# 09_LMS2_RF.net
KiCad netlist of a schematic drawn in Altium Designer
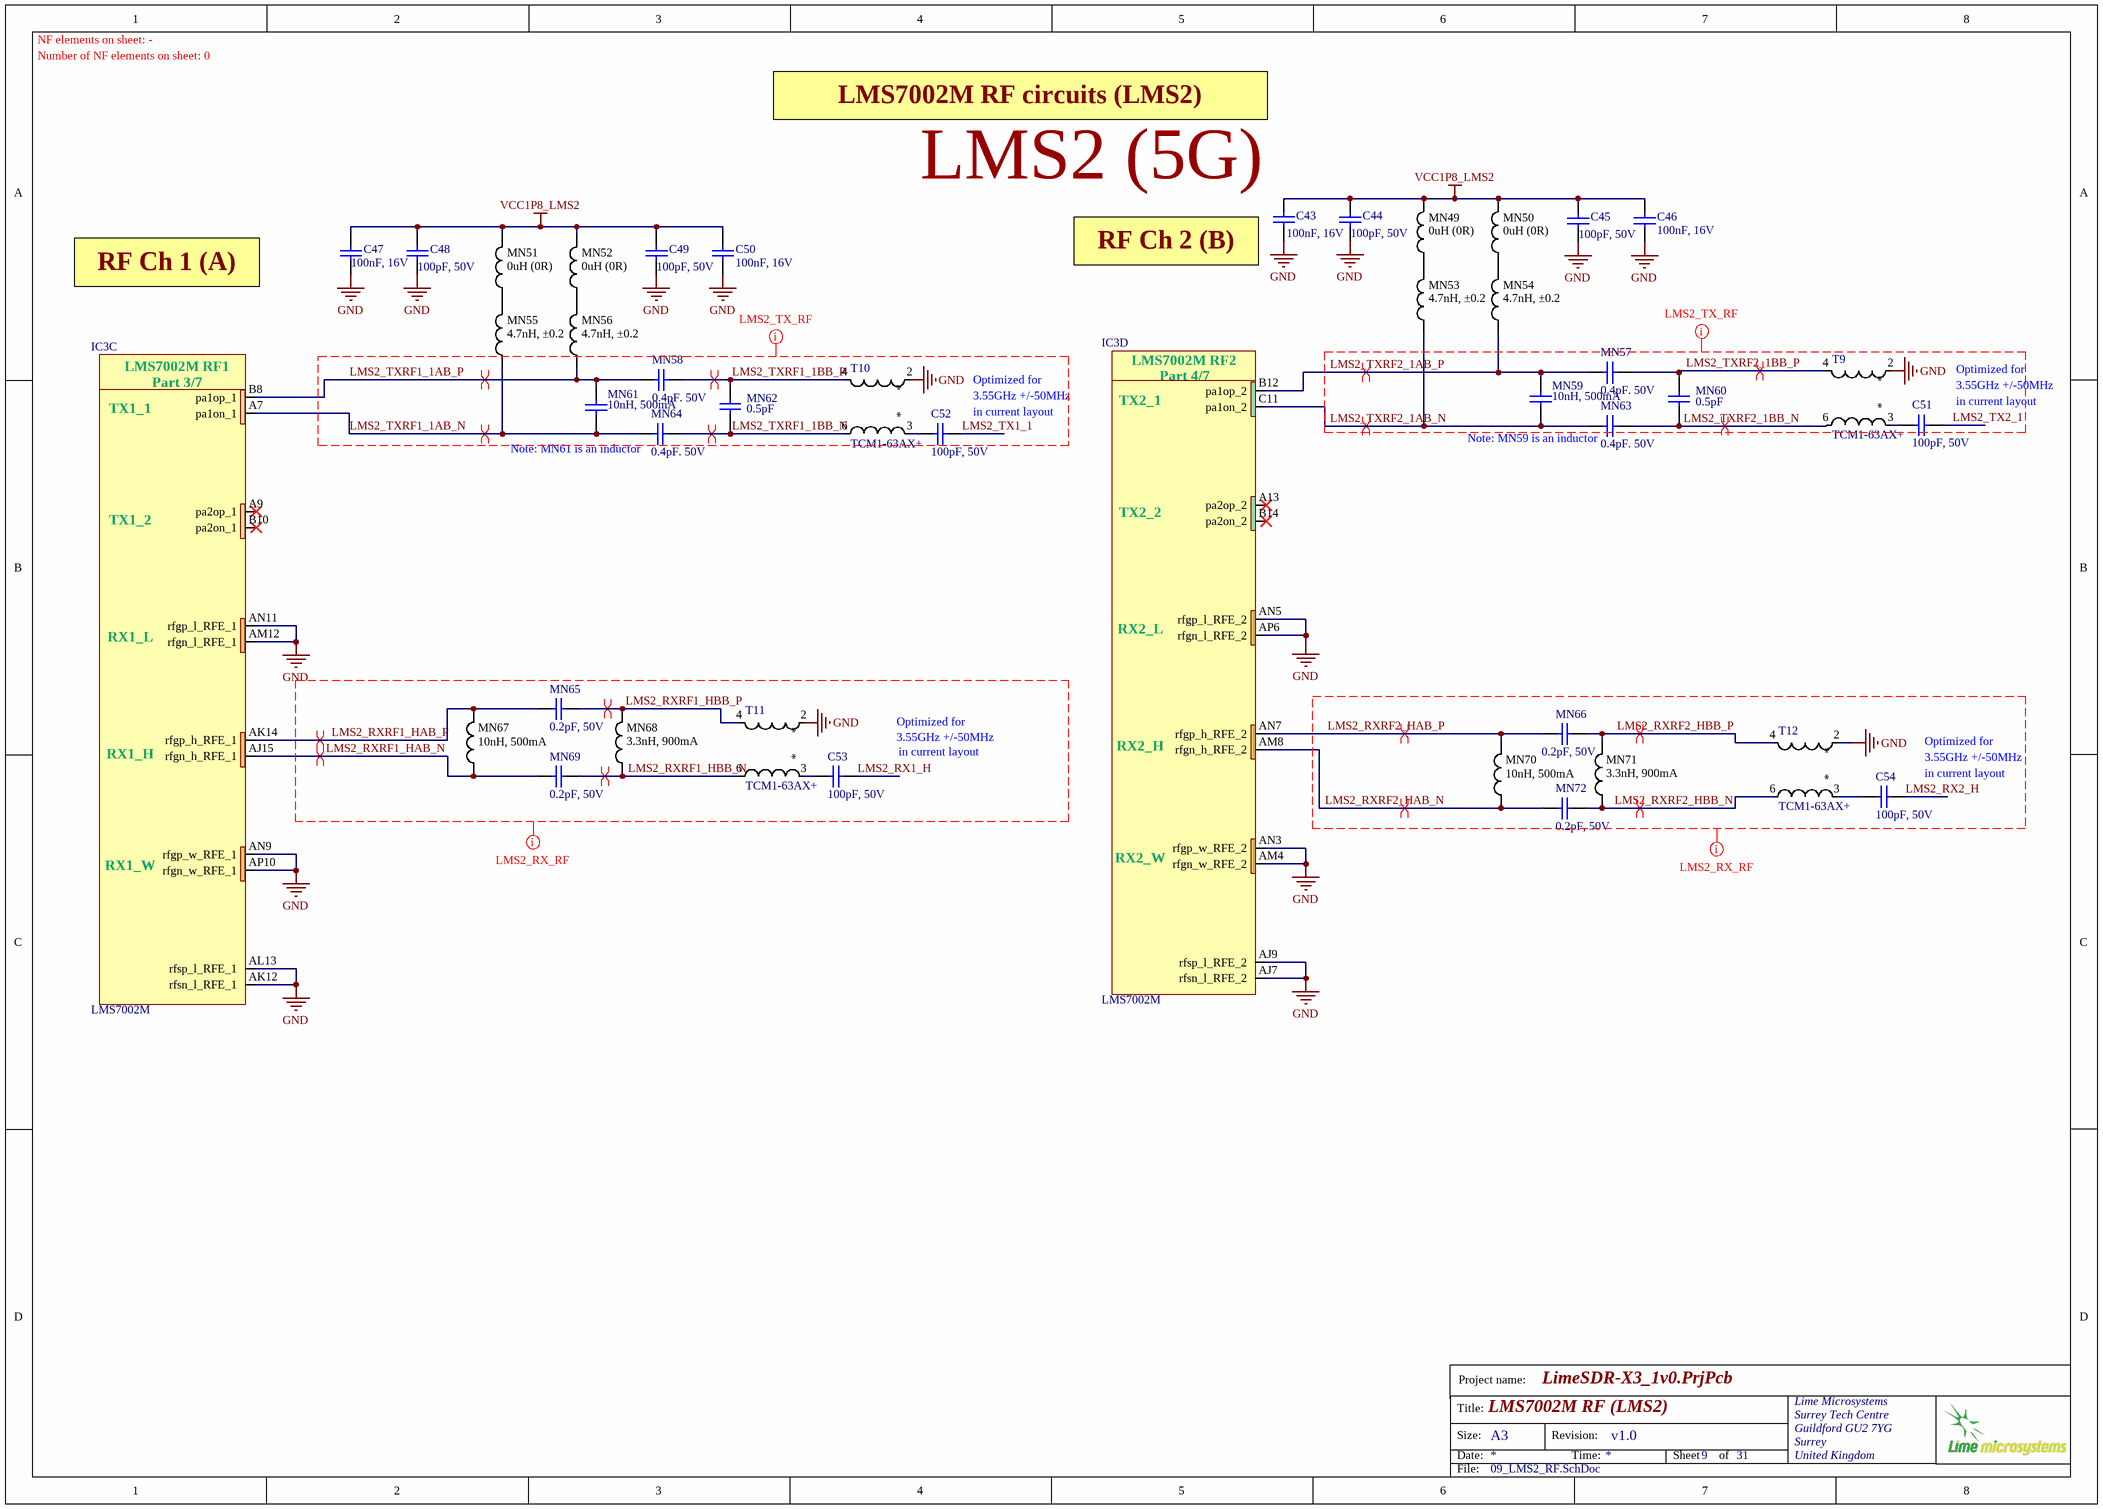
[diagram p0: 09_LMS2_RF.SchDoc]

(export (version "E")
  (design (tool "Eeschema 10.0.6"))
  (components
    (comp (ref "C43")
      (value "100nF, 16V")
      (footprint "CAP0402")
      (fields (field (name "MANUFACTURER") "Murata Electronics") (field (name "TOLERANCE") "10 %"))
      (libsource (lib "LimeMicroAltiumLib_schLib") (part "Cap_0402"))
    )
    (comp (ref "C44")
      (value "100pF, 50V")
      (footprint "CAP0402")
      (fields (field (name "MANUFACTURER") "Yageo") (field (name "TOLERANCE") "±5%"))
      (libsource (lib "") (part "Cap_0402_5"))
    )
    (comp (ref "C45")
      (value "100pF, 50V")
      (footprint "CAP0402")
      (fields (field (name "MANUFACTURER") "Yageo") (field (name "TOLERANCE") "±5%"))
      (libsource (lib "") (part "Cap_0402_5"))
    )
    (comp (ref "C46")
      (value "100nF, 16V")
      (footprint "CAP0402")
      (fields (field (name "MANUFACTURER") "Murata Electronics") (field (name "TOLERANCE") "10 %"))
      (libsource (lib "LimeMicroAltiumLib_schLib") (part "Cap_0402"))
    )
    (comp (ref "C47")
      (value "100nF, 16V")
      (footprint "CAP0402")
      (fields (field (name "MANUFACTURER") "Murata Electronics") (field (name "TOLERANCE") "10 %"))
      (libsource (lib "") (part "Cap_0402_2"))
    )
    (comp (ref "C48")
      (value "100pF, 50V")
      (footprint "CAP0402")
      (fields (field (name "MANUFACTURER") "Yageo") (field (name "TOLERANCE") "±5%"))
      (libsource (lib "") (part "Cap_0402_5"))
    )
    (comp (ref "C49")
      (value "100pF, 50V")
      (footprint "CAP0402")
      (fields (field (name "MANUFACTURER") "Yageo") (field (name "TOLERANCE") "±5%"))
      (libsource (lib "") (part "Cap_0402_5"))
    )
    (comp (ref "C50")
      (value "100nF, 16V")
      (footprint "CAP0402")
      (fields (field (name "MANUFACTURER") "Murata Electronics") (field (name "TOLERANCE") "10 %"))
      (libsource (lib "") (part "Cap_0402_2"))
    )
    (comp (ref "C51")
      (value "100pF, 50V")
      (footprint "CAP0402")
      (fields (field (name "TOLERANCE") "±5%") (field (name "MANUFACTURER") "Yageo"))
      (libsource (lib "") (part "Cap_0402_2"))
    )
    (comp (ref "C52")
      (value "100pF, 50V")
      (footprint "CAP0402")
      (fields (field (name "TOLERANCE") "±5%") (field (name "MANUFACTURER") "Yageo"))
      (libsource (lib "") (part "Cap_0402_2"))
    )
    (comp (ref "C53")
      (value "100pF, 50V")
      (footprint "CAP0402")
      (fields (field (name "TOLERANCE") "±5%") (field (name "MANUFACTURER") "Yageo"))
      (libsource (lib "") (part "Cap_0402_6"))
    )
    (comp (ref "C54")
      (value "100pF, 50V")
      (footprint "CAP0402")
      (fields (field (name "TOLERANCE") "±5%") (field (name "MANUFACTURER") "Yageo"))
      (libsource (lib "") (part "Cap_0402_6"))
    )
    (comp (ref "IC3")
      (value "LMS7002M")
      (footprint "LMS7002M_v5")
      (description "Schematic symbol revision 4. Default footprint - 0.31mm pad")
      (fields (field (name "MANUFACTURER") "Lime Microsystems"))
      (libsource (lib "LimeMicroAltiumLib_schLib_r04") (part "LMS7002Mr4"))
    )
    (comp (ref "MN49")
      (value "0uH (0R)")
      (footprint "RES0603")
      (fields
        (field (name "MANUFACTURER") "Panasonic Electronic Components")
        (field (name "MANUFACTURER PART NUMBER") "ERJ-3GEY0R00V")
        (field (name "TOLERANCE") "Jumper")
      )
      (libsource (lib "") (part "Inductor_0603_1"))
    )
    (comp (ref "MN50")
      (value "0uH (0R)")
      (footprint "RES0603")
      (fields
        (field (name "MANUFACTURER") "Panasonic Electronic Components")
        (field (name "MANUFACTURER PART NUMBER") "ERJ-3GEY0R00V")
        (field (name "TOLERANCE") "Jumper")
      )
      (libsource (lib "") (part "Inductor_0603_1"))
    )
    (comp (ref "MN51")
      (value "0uH (0R)")
      (footprint "RES0603")
      (fields
        (field (name "MANUFACTURER") "Panasonic Electronic Components")
        (field (name "MANUFACTURER PART NUMBER") "ERJ-3GEY0R00V")
        (field (name "TOLERANCE") "Jumper")
      )
      (libsource (lib "") (part "Inductor_0603_1"))
    )
    (comp (ref "MN52")
      (value "0uH (0R)")
      (footprint "RES0603")
      (fields
        (field (name "MANUFACTURER") "Panasonic Electronic Components")
        (field (name "MANUFACTURER PART NUMBER") "ERJ-3GEY0R00V")
        (field (name "TOLERANCE") "Jumper")
      )
      (libsource (lib "") (part "Inductor_0603_1"))
    )
    (comp (ref "MN53")
      (value "4.7nH, ±0.2")
      (footprint "RES0402")
      (fields (field (name "MANUFACTURER") "Murata"))
      (libsource (lib "") (part "Inductor_0603_1"))
    )
    (comp (ref "MN54")
      (value "4.7nH, ±0.2")
      (footprint "RES0402")
      (fields (field (name "MANUFACTURER") "Murata"))
      (libsource (lib "") (part "Inductor_0603_1"))
    )
    (comp (ref "MN55")
      (value "4.7nH, ±0.2")
      (footprint "RES0402")
      (fields (field (name "MANUFACTURER") "Murata"))
      (libsource (lib "") (part "Inductor_0603_1"))
    )
    (comp (ref "MN56")
      (value "4.7nH, ±0.2")
      (footprint "RES0402")
      (fields (field (name "MANUFACTURER") "Murata"))
      (libsource (lib "") (part "Inductor_0603_1"))
    )
    (comp (ref "MN57")
      (value "0.4pF. 50V")
      (footprint "CAP0402")
      (fields (field (name "MANUFACTURER") "Murata"))
      (libsource (lib "") (part "Cap_0402_3"))
    )
    (comp (ref "MN58")
      (value "0.4pF. 50V")
      (footprint "CAP0402")
      (fields (field (name "MANUFACTURER") "Murata"))
      (libsource (lib "") (part "Cap_0402_3"))
    )
    (comp (ref "MN59")
      (value "10nH, 500mA")
      (footprint "CAP0402")
      (fields (field (name "MANUFACTURER") "Murata") (field (name "TOLERANCE") "2%"))
      (libsource (lib "") (part "Cap_0402_7"))
    )
    (comp (ref "MN60")
      (value "0.5pF")
      (footprint "CAP0402")
      (fields (field (name "TOLERANCE") "±0.25pF") (field (name "MANUFACTURER") "Yageo"))
      (libsource (lib "") (part "Cap_0402_2"))
    )
    (comp (ref "MN61")
      (value "10nH, 500mA")
      (footprint "CAP0402")
      (fields (field (name "MANUFACTURER") "Murata") (field (name "TOLERANCE") "2%"))
      (libsource (lib "") (part "Cap_0402_7"))
    )
    (comp (ref "MN62")
      (value "0.5pF")
      (footprint "CAP0402")
      (fields (field (name "TOLERANCE") "±0.25pF") (field (name "MANUFACTURER") "Yageo"))
      (libsource (lib "") (part "Cap_0402_2"))
    )
    (comp (ref "MN63")
      (value "0.4pF. 50V")
      (footprint "CAP0402")
      (fields (field (name "MANUFACTURER") "Murata"))
      (libsource (lib "") (part "Cap_0402_4"))
    )
    (comp (ref "MN64")
      (value "0.4pF. 50V")
      (footprint "CAP0402")
      (fields (field (name "MANUFACTURER") "Murata"))
      (libsource (lib "") (part "Cap_0402_4"))
    )
    (comp (ref "MN65")
      (value "0.2pF, 50V")
      (footprint "CAP0402")
      (fields (field (name "MANUFACTURER") "Murata"))
      (libsource (lib "") (part "Cap_0402_1"))
    )
    (comp (ref "MN66")
      (value "0.2pF, 50V")
      (footprint "CAP0402")
      (fields (field (name "MANUFACTURER") "Murata"))
      (libsource (lib "") (part "Cap_0402_1"))
    )
    (comp (ref "MN67")
      (value "10nH, 500mA")
      (footprint "RES0402")
      (fields (field (name "MANUFACTURER") "Murata") (field (name "TOLERANCE") "2%"))
      (libsource (lib "LimeMicroAltiumLib_schLib") (part "Inductor_0603"))
    )
    (comp (ref "MN68")
      (value "3.3nH, 900mA")
      (footprint "RES0402")
      (fields (field (name "MANUFACTURER") "Murata"))
      (libsource (lib "") (part "Inductor_0603_2"))
    )
    (comp (ref "MN69")
      (value "0.2pF, 50V")
      (footprint "CAP0402")
      (fields (field (name "MANUFACTURER") "Murata"))
      (libsource (lib "") (part "Cap_0402_1"))
    )
    (comp (ref "MN70")
      (value "10nH, 500mA")
      (footprint "RES0402")
      (fields (field (name "MANUFACTURER") "Murata") (field (name "TOLERANCE") "2%"))
      (libsource (lib "LimeMicroAltiumLib_schLib") (part "Inductor_0603"))
    )
    (comp (ref "MN71")
      (value "3.3nH, 900mA")
      (footprint "RES0402")
      (fields (field (name "MANUFACTURER") "Murata"))
      (libsource (lib "") (part "Inductor_0603_2"))
    )
    (comp (ref "MN72")
      (value "0.2pF, 50V")
      (footprint "CAP0402")
      (fields (field (name "MANUFACTURER") "Murata"))
      (libsource (lib "") (part "Cap_0402_1"))
    )
    (comp (ref "T9")
      (value "TCM1-63AX+")
      (footprint "TCM1-63AX+_v2")
      (fields (field (name "MANUFACTURER") "Mini-circuits"))
      (libsource (lib "LimeMicroAltiumLib_schLib") (part "Balun_v2"))
    )
    (comp (ref "T10")
      (value "TCM1-63AX+")
      (footprint "TCM1-63AX+_v2")
      (fields (field (name "MANUFACTURER") "Mini-circuits"))
      (libsource (lib "LimeMicroAltiumLib_schLib") (part "Balun_v2"))
    )
    (comp (ref "T11")
      (value "TCM1-63AX+")
      (footprint "TCM1-63AX+_v2")
      (fields (field (name "MANUFACTURER") "Mini-circuits"))
      (libsource (lib "") (part "Balun_v2_1"))
    )
    (comp (ref "T12")
      (value "TCM1-63AX+")
      (footprint "TCM1-63AX+_v2")
      (fields (field (name "MANUFACTURER") "Mini-circuits"))
      (libsource (lib "") (part "Balun_v2_1"))
    )
  )
  (nets
    (net (code "1") (name "/LMS2_RX1_H") (class "Default")
      (node (ref "C53") (pin "1") (pinfunction "1_1") (pintype "passive"))
    )
    (net (code "2") (name "/LMS2_RX2_H") (class "Default")
      (node (ref "C54") (pin "1") (pinfunction "1_1") (pintype "passive"))
    )
    (net (code "3") (name "/LMS2_RXRF1_HAB_N") (class "Default")
      (node (ref "IC3") (pin "AJ15") (pinfunction "rfgn_h_RFE_1_AJ15") (pintype "passive"))
      (node (ref "MN67") (pin "1") (pinfunction "1_1") (pintype "passive"))
      (node (ref "MN69") (pin "2") (pinfunction "2_2") (pintype "passive"))
    )
    (net (code "4") (name "/LMS2_RXRF1_HAB_P") (class "Default")
      (node (ref "IC3") (pin "AK14") (pinfunction "rfgp_h_RFE_1_AK14") (pintype "passive"))
      (node (ref "MN65") (pin "2") (pinfunction "2_2") (pintype "passive"))
      (node (ref "MN67") (pin "2") (pinfunction "2_2") (pintype "passive"))
    )
    (net (code "5") (name "/LMS2_RXRF1_HBB_N") (class "Default")
      (node (ref "MN68") (pin "1") (pinfunction "1_1") (pintype "passive"))
      (node (ref "MN69") (pin "1") (pinfunction "1_1") (pintype "passive"))
      (node (ref "T11") (pin "6") (pinfunction "6_6") (pintype "passive"))
    )
    (net (code "6") (name "/LMS2_RXRF1_HBB_P") (class "Default")
      (node (ref "MN65") (pin "1") (pinfunction "1_1") (pintype "passive"))
      (node (ref "MN68") (pin "2") (pinfunction "2_2") (pintype "passive"))
      (node (ref "T11") (pin "4") (pinfunction "4_4") (pintype "passive"))
    )
    (net (code "7") (name "/LMS2_RXRF2_HAB_N") (class "Default")
      (node (ref "IC3") (pin "AM8") (pinfunction "rfgn_h_RFE_2_AM8") (pintype "passive"))
      (node (ref "MN70") (pin "1") (pinfunction "1_1") (pintype "passive"))
      (node (ref "MN72") (pin "2") (pinfunction "2_2") (pintype "passive"))
    )
    (net (code "8") (name "/LMS2_RXRF2_HAB_P") (class "Default")
      (node (ref "IC3") (pin "AN7") (pinfunction "rfgp_h_RFE_2_AN7") (pintype "passive"))
      (node (ref "MN66") (pin "2") (pinfunction "2_2") (pintype "passive"))
      (node (ref "MN70") (pin "2") (pinfunction "2_2") (pintype "passive"))
    )
    (net (code "9") (name "/LMS2_RXRF2_HBB_N") (class "Default")
      (node (ref "MN71") (pin "1") (pinfunction "1_1") (pintype "passive"))
      (node (ref "MN72") (pin "1") (pinfunction "1_1") (pintype "passive"))
      (node (ref "T12") (pin "6") (pinfunction "6_6") (pintype "passive"))
    )
    (net (code "10") (name "/LMS2_RXRF2_HBB_P") (class "Default")
      (node (ref "MN66") (pin "1") (pinfunction "1_1") (pintype "passive"))
      (node (ref "MN71") (pin "2") (pinfunction "2_2") (pintype "passive"))
      (node (ref "T12") (pin "4") (pinfunction "4_4") (pintype "passive"))
    )
    (net (code "11") (name "/LMS2_TX1_1") (class "Default")
      (node (ref "C52") (pin "1") (pinfunction "1_1") (pintype "passive"))
    )
    (net (code "12") (name "/LMS2_TX2_1") (class "Default")
      (node (ref "C51") (pin "1") (pinfunction "1_1") (pintype "passive"))
    )
    (net (code "13") (name "/LMS2_TXRF1_1AB_N") (class "Default")
      (node (ref "IC3") (pin "A7") (pinfunction "pa1on_1_A7") (pintype "passive"))
      (node (ref "MN55") (pin "1") (pinfunction "1_1") (pintype "passive"))
      (node (ref "MN61") (pin "2") (pinfunction "2_2") (pintype "passive"))
      (node (ref "MN64") (pin "2") (pinfunction "2_2") (pintype "passive"))
    )
    (net (code "14") (name "/LMS2_TXRF1_1AB_P") (class "Default")
      (node (ref "IC3") (pin "B8") (pinfunction "pa1op_1_B8") (pintype "passive"))
      (node (ref "MN56") (pin "1") (pinfunction "1_1") (pintype "passive"))
      (node (ref "MN58") (pin "2") (pinfunction "2_2") (pintype "passive"))
      (node (ref "MN61") (pin "1") (pinfunction "1_1") (pintype "passive"))
    )
    (net (code "15") (name "/LMS2_TXRF1_1BB_N") (class "Default")
      (node (ref "MN62") (pin "1") (pinfunction "1_1") (pintype "passive"))
      (node (ref "MN64") (pin "1") (pinfunction "1_1") (pintype "passive"))
      (node (ref "T10") (pin "6") (pinfunction "6_6") (pintype "passive"))
    )
    (net (code "16") (name "/LMS2_TXRF1_1BB_P") (class "Default")
      (node (ref "MN58") (pin "1") (pinfunction "1_1") (pintype "passive"))
      (node (ref "MN62") (pin "2") (pinfunction "2_2") (pintype "passive"))
      (node (ref "T10") (pin "4") (pinfunction "4_4") (pintype "passive"))
    )
    (net (code "17") (name "/LMS2_TXRF2_1AB_N") (class "Default")
      (node (ref "IC3") (pin "C11") (pinfunction "pa1on_2_C11") (pintype "passive"))
      (node (ref "MN53") (pin "1") (pinfunction "1_1") (pintype "passive"))
      (node (ref "MN59") (pin "2") (pinfunction "2_2") (pintype "passive"))
      (node (ref "MN63") (pin "2") (pinfunction "2_2") (pintype "passive"))
    )
    (net (code "18") (name "/LMS2_TXRF2_1AB_P") (class "Default")
      (node (ref "IC3") (pin "B12") (pinfunction "pa1op_2_B12") (pintype "passive"))
      (node (ref "MN54") (pin "1") (pinfunction "1_1") (pintype "passive"))
      (node (ref "MN57") (pin "2") (pinfunction "2_2") (pintype "passive"))
      (node (ref "MN59") (pin "1") (pinfunction "1_1") (pintype "passive"))
    )
    (net (code "19") (name "/LMS2_TXRF2_1BB_N") (class "Default")
      (node (ref "MN60") (pin "1") (pinfunction "1_1") (pintype "passive"))
      (node (ref "MN63") (pin "1") (pinfunction "1_1") (pintype "passive"))
      (node (ref "T9") (pin "6") (pinfunction "6_6") (pintype "passive"))
    )
    (net (code "20") (name "/LMS2_TXRF2_1BB_P") (class "Default")
      (node (ref "MN57") (pin "1") (pinfunction "1_1") (pintype "passive"))
      (node (ref "MN60") (pin "2") (pinfunction "2_2") (pintype "passive"))
      (node (ref "T9") (pin "4") (pinfunction "4_4") (pintype "passive"))
    )
    (net (code "21") (name "GND") (class "Default")
      (node (ref "C43") (pin "1") (pinfunction "1_1") (pintype "passive"))
      (node (ref "C44") (pin "1") (pinfunction "1_1") (pintype "passive"))
      (node (ref "C45") (pin "1") (pinfunction "1_1") (pintype "passive"))
      (node (ref "C46") (pin "1") (pinfunction "1_1") (pintype "passive"))
      (node (ref "C47") (pin "1") (pinfunction "1_1") (pintype "passive"))
      (node (ref "C48") (pin "1") (pinfunction "1_1") (pintype "passive"))
      (node (ref "C49") (pin "1") (pinfunction "1_1") (pintype "passive"))
      (node (ref "C50") (pin "1") (pinfunction "1_1") (pintype "passive"))
      (node (ref "IC3") (pin "AJ7") (pinfunction "rfsn_l_RFE_2_AJ7") (pintype "passive"))
      (node (ref "IC3") (pin "AJ9") (pinfunction "rfsp_l_RFE_2_AJ9") (pintype "passive"))
      (node (ref "IC3") (pin "AK12") (pinfunction "rfsn_l_RFE_1_AK12") (pintype "passive"))
      (node (ref "IC3") (pin "AL13") (pinfunction "rfsp_l_RFE_1_AL13") (pintype "passive"))
      (node (ref "IC3") (pin "AM12") (pinfunction "rfgn_l_RFE_1_AM12") (pintype "passive"))
      (node (ref "IC3") (pin "AM4") (pinfunction "rfgn_w_RFE_2_AM4") (pintype "passive"))
      (node (ref "IC3") (pin "AN11") (pinfunction "rfgp_l_RFE_1_AN11") (pintype "passive"))
      (node (ref "IC3") (pin "AN3") (pinfunction "rfgp_w_RFE_2_AN3") (pintype "passive"))
      (node (ref "IC3") (pin "AN5") (pinfunction "rfgp_l_RFE_2_AN5") (pintype "passive"))
      (node (ref "IC3") (pin "AN9") (pinfunction "rfgp_w_RFE_1_AN9") (pintype "passive"))
      (node (ref "IC3") (pin "AP10") (pinfunction "rfgn_w_RFE_1_AP10") (pintype "passive"))
      (node (ref "IC3") (pin "AP6") (pinfunction "rfgn_l_RFE_2_AP6") (pintype "passive"))
      (node (ref "T10") (pin "2") (pinfunction "2_2") (pintype "passive"))
      (node (ref "T11") (pin "2") (pinfunction "2_2") (pintype "passive"))
      (node (ref "T12") (pin "2") (pinfunction "2_2") (pintype "passive"))
      (node (ref "T9") (pin "2") (pinfunction "2_2") (pintype "passive"))
    )
    (net (code "22") (name "Net-(C51-Pad2)") (class "Default")
      (node (ref "C51") (pin "2") (pinfunction "2_2") (pintype "passive"))
      (node (ref "T9") (pin "3") (pinfunction "3_3") (pintype "passive"))
    )
    (net (code "23") (name "Net-(C52-Pad2)") (class "Default")
      (node (ref "C52") (pin "2") (pinfunction "2_2") (pintype "passive"))
      (node (ref "T10") (pin "3") (pinfunction "3_3") (pintype "passive"))
    )
    (net (code "24") (name "Net-(C53-Pad2)") (class "Default")
      (node (ref "C53") (pin "2") (pinfunction "2_2") (pintype "passive"))
      (node (ref "T11") (pin "3") (pinfunction "3_3") (pintype "passive"))
    )
    (net (code "25") (name "Net-(C54-Pad2)") (class "Default")
      (node (ref "C54") (pin "2") (pinfunction "2_2") (pintype "passive"))
      (node (ref "T12") (pin "3") (pinfunction "3_3") (pintype "passive"))
    )
    (net (code "26") (name "Net-(MN49-Pad1)") (class "Default")
      (node (ref "MN49") (pin "1") (pinfunction "1_1") (pintype "passive"))
      (node (ref "MN53") (pin "2") (pinfunction "2_2") (pintype "passive"))
    )
    (net (code "27") (name "Net-(MN50-Pad1)") (class "Default")
      (node (ref "MN50") (pin "1") (pinfunction "1_1") (pintype "passive"))
      (node (ref "MN54") (pin "2") (pinfunction "2_2") (pintype "passive"))
    )
    (net (code "28") (name "Net-(MN51-Pad1)") (class "Default")
      (node (ref "MN51") (pin "1") (pinfunction "1_1") (pintype "passive"))
      (node (ref "MN55") (pin "2") (pinfunction "2_2") (pintype "passive"))
    )
    (net (code "29") (name "Net-(MN52-Pad1)") (class "Default")
      (node (ref "MN52") (pin "1") (pinfunction "1_1") (pintype "passive"))
      (node (ref "MN56") (pin "2") (pinfunction "2_2") (pintype "passive"))
    )
    (net (code "30") (name "VCC1P8_LMS2") (class "Default")
      (node (ref "C43") (pin "2") (pinfunction "2_2") (pintype "passive"))
      (node (ref "C44") (pin "2") (pinfunction "2_2") (pintype "passive"))
      (node (ref "C45") (pin "2") (pinfunction "2_2") (pintype "passive"))
      (node (ref "C46") (pin "2") (pinfunction "2_2") (pintype "passive"))
      (node (ref "C47") (pin "2") (pinfunction "2_2") (pintype "passive"))
      (node (ref "C48") (pin "2") (pinfunction "2_2") (pintype "passive"))
      (node (ref "C49") (pin "2") (pinfunction "2_2") (pintype "passive"))
      (node (ref "C50") (pin "2") (pinfunction "2_2") (pintype "passive"))
      (node (ref "MN49") (pin "2") (pinfunction "2_2") (pintype "passive"))
      (node (ref "MN50") (pin "2") (pinfunction "2_2") (pintype "passive"))
      (node (ref "MN51") (pin "2") (pinfunction "2_2") (pintype "passive"))
      (node (ref "MN52") (pin "2") (pinfunction "2_2") (pintype "passive"))
    )
    (net (code "31") (name "unconnected-(IC3C-pa2on_1-PadB10)") (class "Default")
      (node (ref "IC3") (pin "B10") (pinfunction "pa2on_1_B10") (pintype "passive+no_connect"))
    )
    (net (code "32") (name "unconnected-(IC3C-pa2op_1-PadA9)") (class "Default")
      (node (ref "IC3") (pin "A9") (pinfunction "pa2op_1_A9") (pintype "passive+no_connect"))
    )
    (net (code "33") (name "unconnected-(IC3D-pa2on_2-PadB14)") (class "Default")
      (node (ref "IC3") (pin "B14") (pinfunction "pa2on_2_B14") (pintype "passive+no_connect"))
    )
    (net (code "34") (name "unconnected-(IC3D-pa2op_2-PadA13)") (class "Default")
      (node (ref "IC3") (pin "A13") (pinfunction "pa2op_2_A13") (pintype "passive+no_connect"))
    )
  )
)
